# RS485_ISL8491.net
KiCad netlist of a schematic drawn in Altium Designer
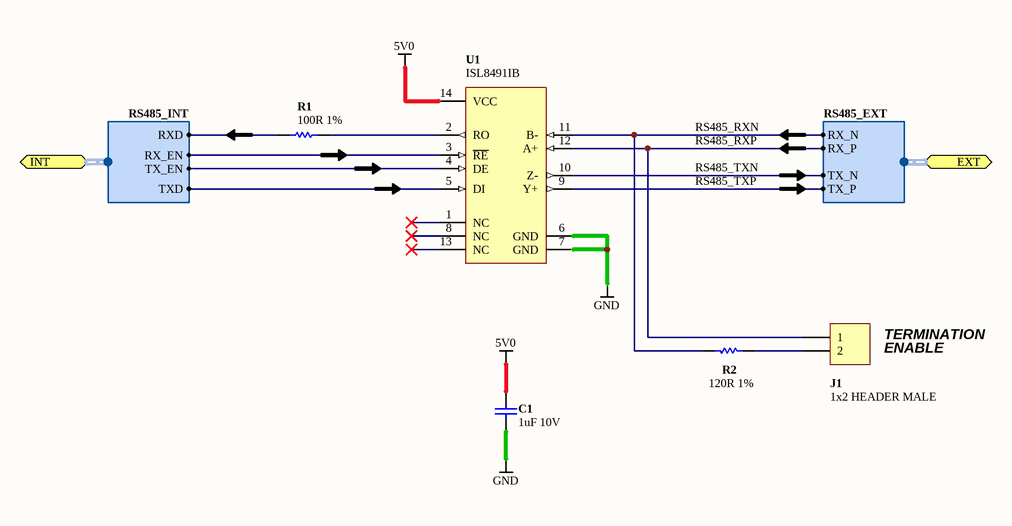
[diagram p0: RS485_ISL8491.SchDoc]

(export (version "E")
  (design (tool "Eeschema 10.0.6"))
  (components
    (comp (ref "C1")
      (value "1uF 10V")
      (footprint "CAPC1005-STAR")
      (description "Capacitor, Ceramic, 1uF 10% 10V 0402 (1005) X5R")
      (fields (field (name "TOLERANCE") "10 %"))
      (libsource (lib "AltiumDesignLibrary") (part "CAP-NP"))
    )
    (comp (ref "J1")
      (value "1x2 HEADER MALE")
      (footprint "HDR1X2")
      (description "Header IDC, 2 x 1 Pin Vertical 2.54mm Pitch (Non-Boxed, Male)")
      (libsource (lib "altium-import") (part "root_0_CON-HDR-1x2-STR_"))
    )
    (comp (ref "R1")
      (value "100R 1%")
      (footprint "RESC1005-STAR")
      (description "Resistor, 100R 1% 0402 (1005)")
      (fields (field (name "TOLERANCE") "1 %"))
      (libsource (lib "altium-import") (part "root_1_RES_"))
    )
    (comp (ref "R2")
      (value "120R 1%")
      (footprint "RESC1005-STAR")
      (description "Resistor, 120R 1% 0402 (1005)")
      (fields (field (name "TOLERANCE") "1 %"))
      (libsource (lib "AltiumDesignLibrary") (part "RES"))
    )
    (comp (ref "U1")
      (value "ISL8491IB")
      (footprint "SOIC127P600-14N")
      (description "ISL8491IB, RS-485/RS-422 Transceivers")
      (libsource (lib "AltiumDesignLibrary") (part "ISL8491IB"))
    )
  )
  (nets
    (net (code "3") (name "/RS485_RXN") (class "Default")
      (node (ref "R2") (pin "1") (pinfunction "1_1") (pintype "passive"))
      (node (ref "U1") (pin "11") (pinfunction "B-_11") (pintype "input"))
    )
    (net (code "4") (name "/RS485_RXP") (class "Default")
      (node (ref "J1") (pin "1") (pinfunction "1_1") (pintype "passive"))
      (node (ref "U1") (pin "12") (pinfunction "A+_12") (pintype "input"))
    )
    (net (code "5") (name "/RS485_TXN") (class "Default")
      (node (ref "U1") (pin "10") (pinfunction "Z-_10") (pintype "output"))
    )
    (net (code "6") (name "/RS485_TXP") (class "Default")
      (node (ref "U1") (pin "9") (pinfunction "Y+_9") (pintype "output"))
    )
    (net (code "7") (name "/RXD") (class "Default")
      (node (ref "R1") (pin "1") (pinfunction "1_1") (pintype "passive"))
    )
    (net (code "8") (name "/RX_EN") (class "Default")
      (node (ref "U1") (pin "3") (pinfunction "~{RE}_3") (pintype "input"))
    )
    (net (code "9") (name "/TXD") (class "Default")
      (node (ref "U1") (pin "5") (pinfunction "DI_5") (pintype "input"))
    )
    (net (code "10") (name "/TX_EN") (class "Default")
      (node (ref "U1") (pin "4") (pinfunction "DE_4") (pintype "input"))
    )
    (net (code "13") (name "5V0") (class "Default")
      (node (ref "C1") (pin "2") (pinfunction "2_2") (pintype "passive"))
      (node (ref "U1") (pin "14") (pinfunction "VCC_14") (pintype "power_in"))
    )
    (net (code "14") (name "GND") (class "Default")
      (node (ref "C1") (pin "1") (pinfunction "1_1") (pintype "passive"))
      (node (ref "U1") (pin "6") (pinfunction "GND_6") (pintype "power_in"))
      (node (ref "U1") (pin "7") (pinfunction "GND_7") (pintype "power_in"))
    )
    (net (code "15") (name "Net-(J1-Pad2)") (class "Default")
      (node (ref "J1") (pin "2") (pinfunction "2_2") (pintype "passive"))
      (node (ref "R2") (pin "2") (pinfunction "2_2") (pintype "passive"))
    )
    (net (code "16") (name "Net-(U1-RO)") (class "Default")
      (node (ref "R1") (pin "2") (pinfunction "2_2") (pintype "passive"))
      (node (ref "U1") (pin "2") (pinfunction "RO_2") (pintype "output"))
    )
    (net (code "17") (name "unconnected-(U1-NC-Pad1)") (class "Default")
      (node (ref "U1") (pin "1") (pinfunction "NC_1") (pintype "passive+no_connect"))
    )
    (net (code "18") (name "unconnected-(U1-NC-Pad8)") (class "Default")
      (node (ref "U1") (pin "8") (pinfunction "NC_8") (pintype "passive+no_connect"))
    )
    (net (code "19") (name "unconnected-(U1-NC-Pad13)") (class "Default")
      (node (ref "U1") (pin "13") (pinfunction "NC_13") (pintype "passive+no_connect"))
    )
  )
)
